# td8655.net
KiCad netlist of a schematic drawn in Altium Designer
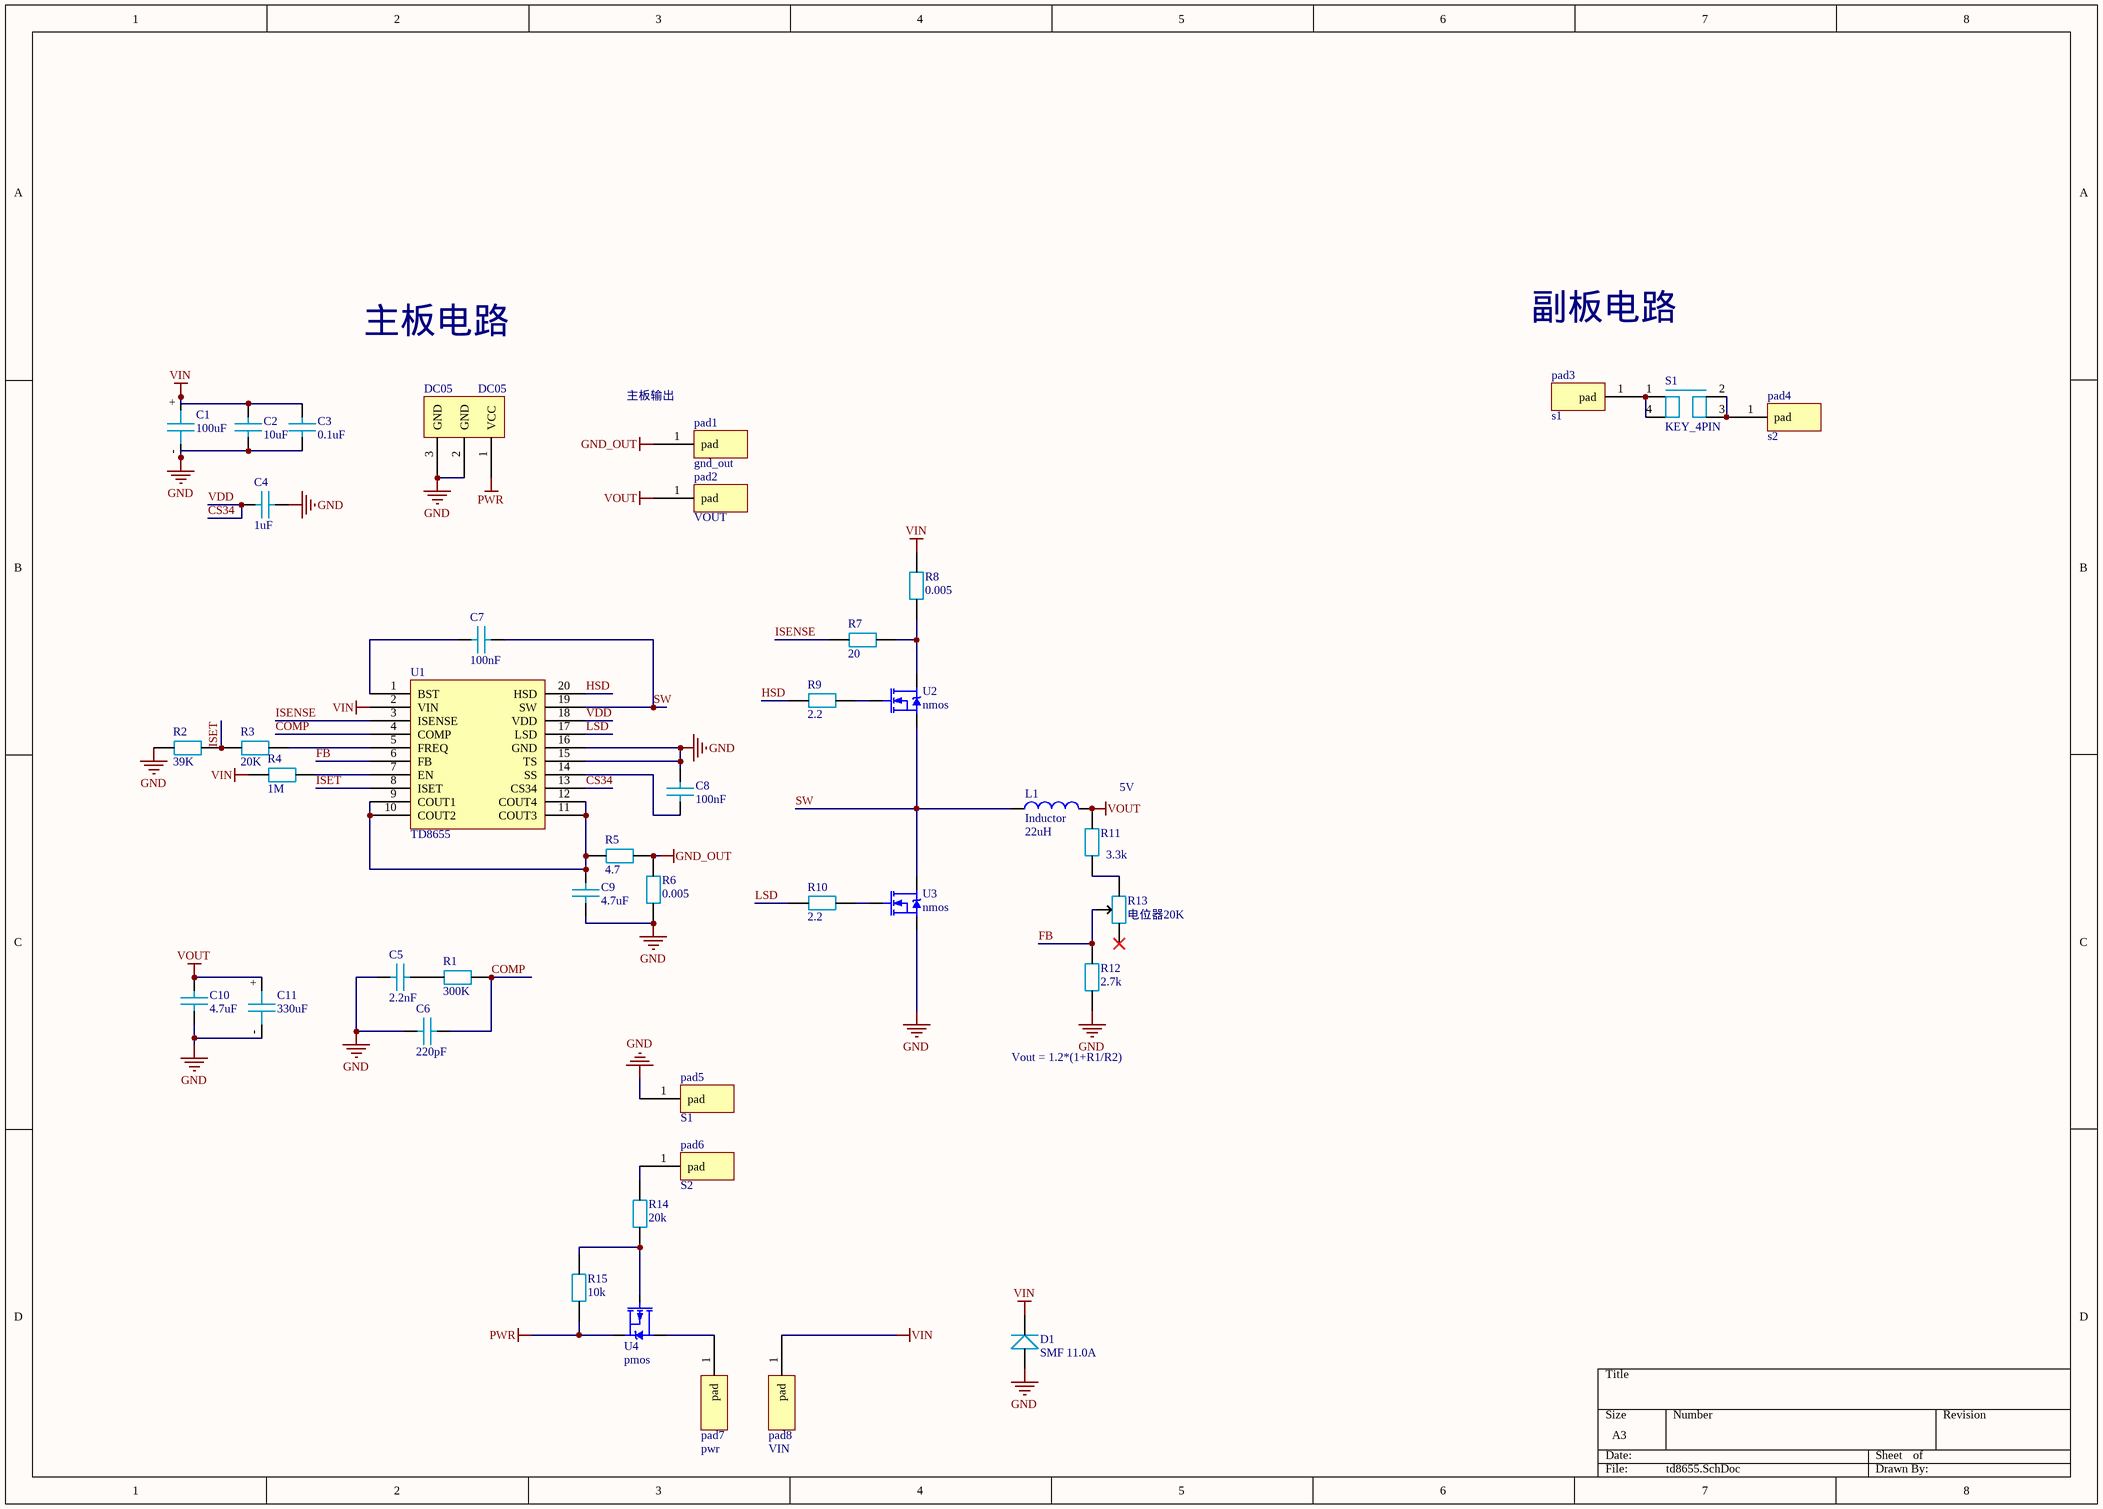
[diagram p0: td8655.SchDoc]

(export (version "E")
  (design (tool "Eeschema 10.0.6"))
  (components
    (comp (ref "C1")
      (value "100uF")
      (footprint "DIP-EC3.5X8X11.5-A")
      (libsource (lib "elin私人订制") (part "CD"))
    )
    (comp (ref "C2") (value "10uF") (footprint "0805_C") (libsource (lib "elin私人订制") (part "C")))
    (comp (ref "C3") (value "0.1uF") (footprint "0805_C") (libsource (lib "elin私人订制") (part "C")))
    (comp (ref "C4") (value "1uF") (footprint "0805_C") (libsource (lib "elin私人订制") (part "C")))
    (comp (ref "C5") (value "2.2nF") (footprint "0805_C") (libsource (lib "elin私人订制") (part "C")))
    (comp (ref "C6") (value "220pF") (footprint "0805_C") (libsource (lib "elin私人订制") (part "C")))
    (comp (ref "C7") (value "100nF") (footprint "0805_C") (libsource (lib "elin私人订制") (part "C")))
    (comp (ref "C8") (value "100nF") (footprint "0805_C") (libsource (lib "elin私人订制") (part "C")))
    (comp (ref "C9") (value "4.7uF") (footprint "0805_C") (libsource (lib "elin私人订制") (part "C")))
    (comp (ref "C10") (value "4.7uF") (footprint "0805_C") (libsource (lib "elin私人订制") (part "C")))
    (comp (ref "C11")
      (value "330uF")
      (footprint "DIP-EC5.0X10X16-A")
      (libsource (lib "elin私人订制") (part "CD"))
    )
    (comp (ref "D1")
      (value "SMF 11.0A")
      (footprint "LC-SOD-123F")
      (libsource (lib "elin私人订制") (part "DIODE"))
    )
    (comp (ref "DC05")
      (value "DC05")
      (footprint "dc003005互通")
      (description "DC05电源")
      (libsource (lib "elin私人订制") (part "DC05"))
    )
    (comp (ref "L1")
      (value "Inductor")
      (footprint "1040电感")
      (fields (field (name "ALTIUM_VALUE") "22uH") (field (name "PUBLISHER") "Altium Limited"))
      (libsource (lib "Miscellaneous Devices") (part "Inductor"))
    )
    (comp (ref "pad1") (value "gnd_out") (footprint "PAD 3*5") (libsource (lib "elin私人订制") (part "pad1")))
    (comp (ref "pad2") (value "VOUT") (footprint "PAD 3*5") (libsource (lib "elin私人订制") (part "pad1")))
    (comp (ref "pad3") (value "s1") (footprint "PAD贴片3*5") (libsource (lib "") (part "pad1_2")))
    (comp (ref "pad4") (value "s2") (footprint "PAD贴片3*5") (libsource (lib "elin私人订制") (part "pad1")))
    (comp (ref "pad5") (value "S1") (footprint "PAD3*3") (libsource (lib "elin私人订制") (part "pad1")))
    (comp (ref "pad6") (value "S2") (footprint "PAD3*3") (libsource (lib "elin私人订制") (part "pad1")))
    (comp (ref "pad7") (value "pwr") (footprint "PAD 3*5") (libsource (lib "") (part "pad1_1")))
    (comp (ref "pad8") (value "VIN") (footprint "PAD 3*5") (libsource (lib "") (part "pad1_1")))
    (comp (ref "R1") (value "300K") (footprint "0805_R") (libsource (lib "elin私人订制") (part "R")))
    (comp (ref "R2") (value "39K") (footprint "0805_R") (libsource (lib "elin私人订制") (part "R")))
    (comp (ref "R3") (value "20K") (footprint "0805_R") (libsource (lib "elin私人订制") (part "R")))
    (comp (ref "R4") (value "1M") (footprint "0805_R") (libsource (lib "elin私人订制") (part "R")))
    (comp (ref "R5") (value "4.7") (footprint "0805_R") (libsource (lib "elin私人订制") (part "R")))
    (comp (ref "R6") (value "0.005") (footprint "1206_R") (libsource (lib "elin私人订制") (part "R")))
    (comp (ref "R7") (value "20") (footprint "0805_R") (libsource (lib "elin私人订制") (part "R")))
    (comp (ref "R8") (value "0.005") (footprint "1206_R") (libsource (lib "elin私人订制") (part "R")))
    (comp (ref "R9") (value "2.2") (footprint "0805_R") (libsource (lib "elin私人订制") (part "R")))
    (comp (ref "R10") (value "2.2") (footprint "0805_R") (libsource (lib "elin私人订制") (part "R")))
    (comp (ref "R11") (value "3.3k") (footprint "0805_R") (libsource (lib "elin私人订制") (part "R")))
    (comp (ref "R12") (value "2.7k") (footprint "0805_R") (libsource (lib "elin私人订制") (part "R")))
    (comp (ref "R13")
      (value "电位器20K")
      (footprint "RK097N电位器")
      (libsource (lib "elin私人订制") (part "potentialmeter"))
    )
    (comp (ref "R14") (value "20k") (footprint "0805_R") (libsource (lib "elin私人订制") (part "R")))
    (comp (ref "R15") (value "10k") (footprint "0805_R") (libsource (lib "elin私人订制") (part "R")))
    (comp (ref "S1")
      (value "KEY_4PIN")
      (footprint "smd4*4轻触开关")
      (libsource (lib "elin私人订制") (part "KEY_4PIN"))
    )
    (comp (ref "U1")
      (value "TD8655")
      (footprint "LC-QFN-20_4x4x05P")
      (libsource (lib "elin私人订制") (part "TD8655"))
    )
    (comp (ref "U2") (value "nmos") (footprint "LC-DFN-8_5x6mm") (libsource (lib "elin私人订制") (part "nmos")))
    (comp (ref "U3") (value "nmos") (footprint "LC-DFN-8_5x6mm") (libsource (lib "elin私人订制") (part "nmos")))
    (comp (ref "U4") (value "pmos") (footprint "LC-DFN-8_5x6mm") (libsource (lib "elin私人订制") (part "pmos")))
  )
  (nets
    (net (code "1") (name "/COMP") (class "Default")
      (node (ref "C6") (pin "2") (pinfunction "2_2") (pintype "passive"))
      (node (ref "R1") (pin "2") (pinfunction "2_2") (pintype "passive"))
      (node (ref "U1") (pin "4") (pinfunction "COMP_4") (pintype "passive"))
    )
    (net (code "2") (name "/CS34") (class "Default")
      (node (ref "C4") (pin "2") (pinfunction "2_2") (pintype "passive"))
      (node (ref "U1") (pin "13") (pinfunction "CS34_13") (pintype "passive"))
      (node (ref "U1") (pin "18") (pinfunction "VDD_18") (pintype "passive"))
    )
    (net (code "3") (name "/FB") (class "Default")
      (node (ref "R12") (pin "2") (pinfunction "2_2") (pintype "passive"))
      (node (ref "R13") (pin "2") (pinfunction "2_2") (pintype "passive"))
      (node (ref "U1") (pin "6") (pinfunction "FB_6") (pintype "passive"))
    )
    (net (code "4") (name "/HSD") (class "Default")
      (node (ref "R9") (pin "2") (pinfunction "2_2") (pintype "passive"))
      (node (ref "U1") (pin "20") (pinfunction "HSD_20") (pintype "passive"))
    )
    (net (code "5") (name "/ISENSE") (class "Default")
      (node (ref "R7") (pin "1") (pinfunction "1_1") (pintype "passive"))
      (node (ref "U1") (pin "3") (pinfunction "ISENSE_3") (pintype "passive"))
    )
    (net (code "6") (name "/ISET") (class "Default")
      (node (ref "R2") (pin "2") (pinfunction "2_2") (pintype "passive"))
      (node (ref "R3") (pin "1") (pinfunction "1_1") (pintype "passive"))
      (node (ref "U1") (pin "8") (pinfunction "ISET_8") (pintype "passive"))
    )
    (net (code "7") (name "/LSD") (class "Default")
      (node (ref "R10") (pin "2") (pinfunction "2_2") (pintype "passive"))
      (node (ref "U1") (pin "17") (pinfunction "LSD_17") (pintype "passive"))
    )
    (net (code "8") (name "/SW") (class "Default")
      (node (ref "C7") (pin "1") (pinfunction "1_1") (pintype "passive"))
      (node (ref "L1") (pin "1") (pinfunction "1_1") (pintype "passive"))
      (node (ref "U1") (pin "19") (pinfunction "SW_19") (pintype "passive"))
      (node (ref "U2") (pin "S") (pinfunction "S_S") (pintype "passive"))
      (node (ref "U3") (pin "D") (pinfunction "D_D") (pintype "passive"))
    )
    (net (code "9") (name "GND") (class "Default")
      (node (ref "C1") (pin "-") (pinfunction "2_-") (pintype "passive"))
      (node (ref "C10") (pin "1") (pinfunction "1_1") (pintype "passive"))
      (node (ref "C11") (pin "-") (pinfunction "2_-") (pintype "passive"))
      (node (ref "C2") (pin "1") (pinfunction "1_1") (pintype "passive"))
      (node (ref "C3") (pin "1") (pinfunction "1_1") (pintype "passive"))
      (node (ref "C4") (pin "1") (pinfunction "1_1") (pintype "passive"))
      (node (ref "C5") (pin "1") (pinfunction "1_1") (pintype "passive"))
      (node (ref "C6") (pin "1") (pinfunction "1_1") (pintype "passive"))
      (node (ref "C8") (pin "2") (pinfunction "2_2") (pintype "passive"))
      (node (ref "C9") (pin "1") (pinfunction "1_1") (pintype "passive"))
      (node (ref "D1") (pin "2") (pinfunction "2_2") (pintype "passive"))
      (node (ref "DC05") (pin "2") (pinfunction "GND_2") (pintype "passive"))
      (node (ref "DC05") (pin "3") (pinfunction "GND_3") (pintype "passive"))
      (node (ref "R12") (pin "1") (pinfunction "1_1") (pintype "passive"))
      (node (ref "R2") (pin "1") (pinfunction "1_1") (pintype "passive"))
      (node (ref "R6") (pin "1") (pinfunction "1_1") (pintype "passive"))
      (node (ref "U1") (pin "15") (pinfunction "TS_15") (pintype "passive"))
      (node (ref "U1") (pin "16") (pinfunction "GND_16") (pintype "passive"))
      (node (ref "U3") (pin "S") (pinfunction "S_S") (pintype "passive"))
      (node (ref "pad5") (pin "1") (pinfunction "pad_1") (pintype "passive"))
    )
    (net (code "10") (name "GND_OUT") (class "Default")
      (node (ref "R5") (pin "2") (pinfunction "2_2") (pintype "passive"))
      (node (ref "R6") (pin "2") (pinfunction "2_2") (pintype "passive"))
      (node (ref "pad1") (pin "1") (pinfunction "pad_1") (pintype "passive"))
    )
    (net (code "11") (name "Net-(C5-Pad2)") (class "Default")
      (node (ref "C5") (pin "2") (pinfunction "2_2") (pintype "passive"))
      (node (ref "R1") (pin "1") (pinfunction "1_1") (pintype "passive"))
    )
    (net (code "12") (name "Net-(R7-Pad2)") (class "Default")
      (node (ref "R7") (pin "2") (pinfunction "2_2") (pintype "passive"))
      (node (ref "R8") (pin "1") (pinfunction "1_1") (pintype "passive"))
      (node (ref "U2") (pin "D") (pinfunction "D_D") (pintype "passive"))
    )
    (net (code "13") (name "Net-(R9-Pad1)") (class "Default")
      (node (ref "R9") (pin "1") (pinfunction "1_1") (pintype "passive"))
      (node (ref "U2") (pin "G") (pinfunction "G_G") (pintype "passive"))
    )
    (net (code "14") (name "Net-(R10-Pad1)") (class "Default")
      (node (ref "R10") (pin "1") (pinfunction "1_1") (pintype "passive"))
      (node (ref "U3") (pin "G") (pinfunction "G_G") (pintype "passive"))
    )
    (net (code "15") (name "Net-(R11-Pad1)") (class "Default")
      (node (ref "R11") (pin "1") (pinfunction "1_1") (pintype "passive"))
      (node (ref "R13") (pin "3") (pinfunction "3_3") (pintype "passive"))
    )
    (net (code "16") (name "Net-(R14-Pad1)") (class "Default")
      (node (ref "R14") (pin "1") (pinfunction "1_1") (pintype "passive"))
      (node (ref "R15") (pin "2") (pinfunction "2_2") (pintype "passive"))
      (node (ref "U4") (pin "G") (pinfunction "G_G") (pintype "passive"))
    )
    (net (code "17") (name "Net-(U1-BST)") (class "Default")
      (node (ref "C7") (pin "2") (pinfunction "2_2") (pintype "passive"))
      (node (ref "U1") (pin "1") (pinfunction "BST_1") (pintype "passive"))
    )
    (net (code "18") (name "Net-(U1-COUT1)") (class "Default")
      (node (ref "C9") (pin "2") (pinfunction "2_2") (pintype "passive"))
      (node (ref "R5") (pin "1") (pinfunction "1_1") (pintype "passive"))
      (node (ref "U1") (pin "10") (pinfunction "COUT2_10") (pintype "passive"))
      (node (ref "U1") (pin "11") (pinfunction "COUT3_11") (pintype "passive"))
      (node (ref "U1") (pin "12") (pinfunction "COUT4_12") (pintype "passive"))
      (node (ref "U1") (pin "9") (pinfunction "COUT1_9") (pintype "passive"))
    )
    (net (code "19") (name "Net-(U1-EN)") (class "Default")
      (node (ref "R4") (pin "2") (pinfunction "2_2") (pintype "passive"))
      (node (ref "U1") (pin "7") (pinfunction "EN_7") (pintype "passive"))
    )
    (net (code "20") (name "Net-(U1-FREQ)") (class "Default")
      (node (ref "R3") (pin "2") (pinfunction "2_2") (pintype "passive"))
      (node (ref "U1") (pin "5") (pinfunction "FREQ_5") (pintype "passive"))
    )
    (net (code "21") (name "Net-(U1-SS)") (class "Default")
      (node (ref "C8") (pin "1") (pinfunction "1_1") (pintype "passive"))
      (node (ref "U1") (pin "14") (pinfunction "SS_14") (pintype "passive"))
    )
    (net (code "22") (name "Net-(pad3-pad)") (class "Default")
      (node (ref "S1") (pin "1") (pinfunction "1_1") (pintype "passive"))
      (node (ref "S1") (pin "4") (pinfunction "4_4") (pintype "passive"))
      (node (ref "pad3") (pin "1") (pinfunction "pad_1") (pintype "passive"))
    )
    (net (code "23") (name "Net-(pad4-pad)") (class "Default")
      (node (ref "S1") (pin "2") (pinfunction "2_2") (pintype "passive"))
      (node (ref "S1") (pin "3") (pinfunction "3_3") (pintype "passive"))
      (node (ref "pad4") (pin "1") (pinfunction "pad_1") (pintype "passive"))
    )
    (net (code "24") (name "Net-(pad6-pad)") (class "Default")
      (node (ref "R14") (pin "2") (pinfunction "2_2") (pintype "passive"))
      (node (ref "pad6") (pin "1") (pinfunction "pad_1") (pintype "passive"))
    )
    (net (code "25") (name "Net-(pad7-pad)") (class "Default")
      (node (ref "U4") (pin "D") (pinfunction "D_D") (pintype "passive"))
      (node (ref "pad7") (pin "1") (pinfunction "pad_1") (pintype "passive"))
    )
    (net (code "26") (name "PWR") (class "Default")
      (node (ref "DC05") (pin "1") (pinfunction "VCC_1") (pintype "passive"))
      (node (ref "R15") (pin "1") (pinfunction "1_1") (pintype "passive"))
      (node (ref "U4") (pin "S") (pinfunction "S_S") (pintype "passive"))
    )
    (net (code "27") (name "VIN") (class "Default")
      (node (ref "C1") (pin "+") (pinfunction "1_+") (pintype "passive"))
      (node (ref "C2") (pin "2") (pinfunction "2_2") (pintype "passive"))
      (node (ref "C3") (pin "2") (pinfunction "2_2") (pintype "passive"))
      (node (ref "D1") (pin "1") (pinfunction "1_1") (pintype "passive"))
      (node (ref "R4") (pin "1") (pinfunction "1_1") (pintype "passive"))
      (node (ref "R8") (pin "2") (pinfunction "2_2") (pintype "passive"))
      (node (ref "U1") (pin "2") (pinfunction "VIN_2") (pintype "passive"))
      (node (ref "pad8") (pin "1") (pinfunction "pad_1") (pintype "passive"))
    )
    (net (code "28") (name "VOUT") (class "Default")
      (node (ref "C10") (pin "2") (pinfunction "2_2") (pintype "passive"))
      (node (ref "C11") (pin "+") (pinfunction "1_+") (pintype "passive"))
      (node (ref "L1") (pin "2") (pinfunction "2_2") (pintype "passive"))
      (node (ref "R11") (pin "2") (pinfunction "2_2") (pintype "passive"))
      (node (ref "pad2") (pin "1") (pinfunction "pad_1") (pintype "passive"))
    )
    (net (code "29") (name "unconnected-(R13-Pad1)") (class "Default")
      (node (ref "R13") (pin "1") (pinfunction "1_1") (pintype "passive+no_connect"))
    )
  )
)
